# BSPD_Test_Board_rev3.net
KiCad netlist of a schematic drawn in EAGLE
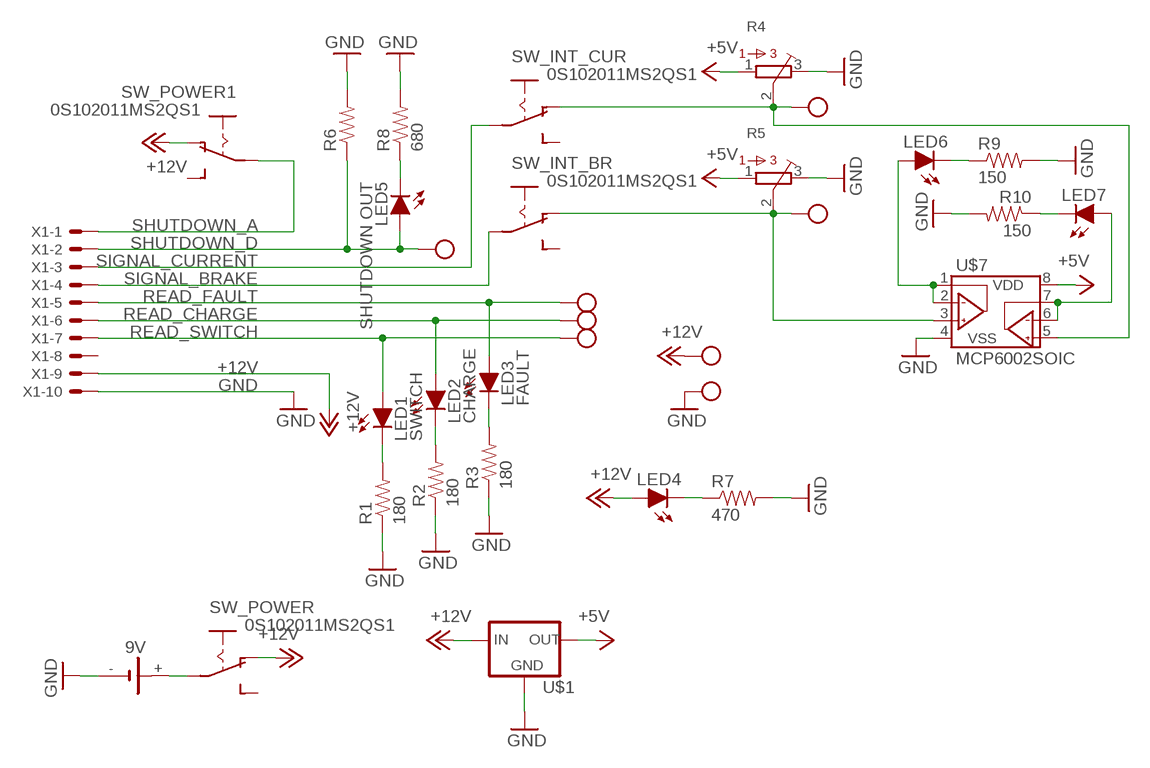
[diagram p0: schematic, sheet 1]

(export (version "E")
  (design (tool "Eeschema 10.0.6"))
  (components
    (comp (ref "9V")
      (value "1291-79")
      (footprint "eagle-import:1291-79")
      (libsource (lib "eagle-import") (part "1291-79"))
    )
    (comp (ref "LED1")
      (value "SWITCH")
      (footprint "eagle-import:LED-5MM")
      (libsource (lib "eagle-import") (part "LED-5MM"))
    )
    (comp (ref "LED2")
      (value "CHARGE")
      (footprint "eagle-import:LED-5MM")
      (libsource (lib "eagle-import") (part "LED-5MM"))
    )
    (comp (ref "LED3")
      (value "FAULT")
      (footprint "eagle-import:LED-5MM")
      (libsource (lib "eagle-import") (part "LED-5MM"))
    )
    (comp (ref "LED4")
      (value "LED-0805")
      (footprint "eagle-import:LED-805")
      (libsource (lib "eagle-import") (part "LED-0805"))
    )
    (comp (ref "LED5")
      (value "SHUTDOWN OUT")
      (footprint "eagle-import:LED-5MM")
      (libsource (lib "eagle-import") (part "LED-5MM"))
    )
    (comp (ref "LED6")
      (value "LED-0805")
      (footprint "eagle-import:LED-805")
      (libsource (lib "eagle-import") (part "LED-0805"))
    )
    (comp (ref "LED7")
      (value "LED-0805")
      (footprint "eagle-import:LED-805")
      (libsource (lib "eagle-import") (part "LED-0805"))
    )
    (comp (ref "R1")
      (value "180")
      (footprint "eagle-import:0805")
      (libsource (lib "eagle-import") (part "RESISTOR0805-RES"))
    )
    (comp (ref "R2")
      (value "180")
      (footprint "eagle-import:0805")
      (libsource (lib "eagle-import") (part "RESISTOR0805-RES"))
    )
    (comp (ref "R3")
      (value "180")
      (footprint "eagle-import:0805")
      (libsource (lib "eagle-import") (part "RESISTOR0805-RES"))
    )
    (comp (ref "R4")
      (value "TRIMPOT_3296C")
      (footprint "eagle-import:TRIMPOT_3296")
      (libsource (lib "eagle-import") (part "TRIMPOT_3296C"))
    )
    (comp (ref "R5")
      (value "TRIMPOT_3296C")
      (footprint "eagle-import:TRIMPOT_3296")
      (libsource (lib "eagle-import") (part "TRIMPOT_3296C"))
    )
    (comp (ref "R6")
      (value "RESISTORPTH-1/2W")
      (footprint "eagle-import:AXIAL-0.5")
      (libsource (lib "eagle-import") (part "RESISTORPTH-1/2W"))
    )
    (comp (ref "R7")
      (value "470")
      (footprint "eagle-import:0805")
      (libsource (lib "eagle-import") (part "RESISTOR0805-RES"))
    )
    (comp (ref "R8")
      (value "680")
      (footprint "eagle-import:0805")
      (libsource (lib "eagle-import") (part "RESISTOR0805-RES"))
    )
    (comp (ref "R9")
      (value "150")
      (footprint "eagle-import:0805")
      (libsource (lib "eagle-import") (part "RESISTOR0805-RES"))
    )
    (comp (ref "R10")
      (value "150")
      (footprint "eagle-import:0805")
      (libsource (lib "eagle-import") (part "RESISTOR0805-RES"))
    )
    (comp (ref "SW_INT_BR")
      (value "0S102011MS2QS1")
      (footprint "eagle-import:0S102011MS2QS1")
      (libsource (lib "eagle-import") (part "0S102011MS2QS1"))
    )
    (comp (ref "SW_INT_CUR")
      (value "0S102011MS2QS1")
      (footprint "eagle-import:0S102011MS2QS1")
      (libsource (lib "eagle-import") (part "0S102011MS2QS1"))
    )
    (comp (ref "SW_POWER")
      (value "0S102011MS2QS1")
      (footprint "eagle-import:0S102011MS2QS1")
      (libsource (lib "eagle-import") (part "0S102011MS2QS1"))
    )
    (comp (ref "SW_POWER1")
      (value "0S102011MS2QS1")
      (footprint "eagle-import:0S102011MS2QS1")
      (libsource (lib "eagle-import") (part "0S102011MS2QS1"))
    )
    (comp (ref "U$1")
      (value "5VREG_LM340-NLM340MPX-5.0/NOPB")
      (footprint "eagle-import:SOT223")
      (libsource (lib "eagle-import") (part "5VREG_LM340-NLM340MPX-5.0/NOPB"))
    )
    (comp (ref "U$2")
      (value "TEST_POINT")
      (footprint "eagle-import:TEST_POINT")
      (libsource (lib "eagle-import") (part "TEST_POINT"))
    )
    (comp (ref "U$3")
      (value "TEST_POINT")
      (footprint "eagle-import:TEST_POINT")
      (libsource (lib "eagle-import") (part "TEST_POINT"))
    )
    (comp (ref "U$4")
      (value "TEST_POINT")
      (footprint "eagle-import:TEST_POINT")
      (libsource (lib "eagle-import") (part "TEST_POINT"))
    )
    (comp (ref "U$5")
      (value "TEST_POINT")
      (footprint "eagle-import:TEST_POINT")
      (libsource (lib "eagle-import") (part "TEST_POINT"))
    )
    (comp (ref "U$6")
      (value "TEST_POINT")
      (footprint "eagle-import:TEST_POINT")
      (libsource (lib "eagle-import") (part "TEST_POINT"))
    )
    (comp (ref "U$7")
      (value "MCP6002SOIC")
      (footprint "eagle-import:SOIC-08")
      (libsource (lib "eagle-import") (part "MCP6002SOIC"))
    )
    (comp (ref "U$8")
      (value "TEST_POINT")
      (footprint "eagle-import:TEST_POINT")
      (libsource (lib "eagle-import") (part "TEST_POINT"))
    )
    (comp (ref "U$9")
      (value "TEST_POINT")
      (footprint "eagle-import:TEST_POINT")
      (libsource (lib "eagle-import") (part "TEST_POINT"))
    )
    (comp (ref "U$10")
      (value "TEST_POINT")
      (footprint "eagle-import:TEST_POINT")
      (libsource (lib "eagle-import") (part "TEST_POINT"))
    )
    (comp (ref "X1")
      (value "CONNECTOR-10")
      (footprint "eagle-import:MINIFIT_5566-10")
      (libsource (lib "eagle-import") (part "CONNECTOR-10"))
    )
  )
  (nets
    (net (code "1") (name "+5V") (class "Default")
      (node (ref "R4") (pin "1") (pinfunction "1_1") (pintype "passive"))
      (node (ref "R5") (pin "1") (pinfunction "1_1") (pintype "passive"))
      (node (ref "U$1") (pin "3") (pinfunction "OUT_3") (pintype "output"))
      (node (ref "U$7") (pin "8") (pinfunction "VDD_8") (pintype "passive"))
    )
    (net (code "2") (name "+12V") (class "Default")
      (node (ref "LED4") (pin "A") (pinfunction "A_A") (pintype "passive"))
      (node (ref "SW_POWER") (pin "P$1") (pinfunction "O_P$1") (pintype "passive"))
      (node (ref "SW_POWER1") (pin "P$1") (pinfunction "O_P$1") (pintype "passive"))
      (node (ref "U$1") (pin "1") (pinfunction "IN_1") (pintype "input"))
      (node (ref "U$5") (pin "P$1") (pinfunction "P$1_P$1") (pintype "bidirectional"))
      (node (ref "X1") (pin "9") (pinfunction "S_9") (pintype "passive"))
    )
    (net (code "3") (name "/READ_CHARGE") (class "Default")
      (node (ref "LED2") (pin "A") (pinfunction "A_A") (pintype "passive"))
      (node (ref "U$9") (pin "P$1") (pinfunction "P$1_P$1") (pintype "bidirectional"))
      (node (ref "X1") (pin "6") (pinfunction "S_6") (pintype "passive"))
    )
    (net (code "4") (name "/READ_FAULT") (class "Default")
      (node (ref "LED3") (pin "A") (pinfunction "A_A") (pintype "passive"))
      (node (ref "U$8") (pin "P$1") (pinfunction "P$1_P$1") (pintype "bidirectional"))
      (node (ref "X1") (pin "5") (pinfunction "S_5") (pintype "passive"))
    )
    (net (code "5") (name "/READ_SWITCH") (class "Default")
      (node (ref "LED1") (pin "A") (pinfunction "A_A") (pintype "passive"))
      (node (ref "U$10") (pin "P$1") (pinfunction "P$1_P$1") (pintype "bidirectional"))
      (node (ref "X1") (pin "7") (pinfunction "S_7") (pintype "passive"))
    )
    (net (code "6") (name "/SHUTDOWN_D") (class "Default")
      (node (ref "LED5") (pin "A") (pinfunction "A_A") (pintype "passive"))
      (node (ref "R6") (pin "P$1") (pinfunction "1_P$1") (pintype "passive"))
      (node (ref "U$4") (pin "P$1") (pinfunction "P$1_P$1") (pintype "bidirectional"))
      (node (ref "X1") (pin "2") (pinfunction "S_2") (pintype "passive"))
    )
    (net (code "7") (name "/SIGNAL_BRAKE") (class "Default")
      (node (ref "SW_INT_BR") (pin "P$2") (pinfunction "P_P$2") (pintype "passive"))
      (node (ref "X1") (pin "4") (pinfunction "S_4") (pintype "passive"))
    )
    (net (code "8") (name "/SIGNAL_CURRENT") (class "Default")
      (node (ref "SW_INT_CUR") (pin "P$2") (pinfunction "P_P$2") (pintype "passive"))
      (node (ref "X1") (pin "3") (pinfunction "S_3") (pintype "passive"))
    )
    (net (code "9") (name "GND") (class "Default")
      (node (ref "9V") (pin "-") (pinfunction "-_-") (pintype "passive"))
      (node (ref "R1") (pin "1") (pinfunction "1_1") (pintype "passive"))
      (node (ref "R10") (pin "2") (pinfunction "2_2") (pintype "passive"))
      (node (ref "R2") (pin "1") (pinfunction "1_1") (pintype "passive"))
      (node (ref "R3") (pin "1") (pinfunction "1_1") (pintype "passive"))
      (node (ref "R4") (pin "3") (pinfunction "3_3") (pintype "passive"))
      (node (ref "R5") (pin "3") (pinfunction "3_3") (pintype "passive"))
      (node (ref "R6") (pin "P$2") (pinfunction "2_P$2") (pintype "passive"))
      (node (ref "R7") (pin "2") (pinfunction "2_2") (pintype "passive"))
      (node (ref "R8") (pin "2") (pinfunction "2_2") (pintype "passive"))
      (node (ref "R9") (pin "2") (pinfunction "2_2") (pintype "passive"))
      (node (ref "U$1") (pin "2") (pinfunction "GND_2") (pintype "input"))
      (node (ref "U$1") (pin "4") (pinfunction "GND_4") (pintype "input"))
      (node (ref "U$6") (pin "P$1") (pinfunction "P$1_P$1") (pintype "bidirectional"))
      (node (ref "U$7") (pin "4") (pinfunction "VSS_4") (pintype "passive"))
      (node (ref "X1") (pin "10") (pinfunction "S_10") (pintype "passive"))
    )
    (net (code "10") (name "Net-(LED1-C)") (class "Default")
      (node (ref "LED1") (pin "K") (pinfunction "C_K") (pintype "passive"))
      (node (ref "R1") (pin "2") (pinfunction "2_2") (pintype "passive"))
    )
    (net (code "11") (name "Net-(LED2-C)") (class "Default")
      (node (ref "LED2") (pin "K") (pinfunction "C_K") (pintype "passive"))
      (node (ref "R2") (pin "2") (pinfunction "2_2") (pintype "passive"))
    )
    (net (code "12") (name "Net-(LED3-C)") (class "Default")
      (node (ref "LED3") (pin "K") (pinfunction "C_K") (pintype "passive"))
      (node (ref "R3") (pin "2") (pinfunction "2_2") (pintype "passive"))
    )
    (net (code "13") (name "Net-(LED4-PadC)") (class "Default")
      (node (ref "LED4") (pin "C") (pinfunction "C_C") (pintype "passive"))
      (node (ref "R7") (pin "1") (pinfunction "1_1") (pintype "passive"))
    )
    (net (code "14") (name "Net-(LED5-C)") (class "Default")
      (node (ref "LED5") (pin "K") (pinfunction "C_K") (pintype "passive"))
      (node (ref "R8") (pin "1") (pinfunction "1_1") (pintype "passive"))
    )
    (net (code "15") (name "Net-(LED6-PadC)") (class "Default")
      (node (ref "LED6") (pin "C") (pinfunction "C_C") (pintype "passive"))
      (node (ref "R9") (pin "1") (pinfunction "1_1") (pintype "passive"))
    )
    (net (code "16") (name "Net-(LED7-PadC)") (class "Default")
      (node (ref "LED7") (pin "C") (pinfunction "C_C") (pintype "passive"))
      (node (ref "R10") (pin "1") (pinfunction "1_1") (pintype "passive"))
    )
    (net (code "17") (name "Net-(SW_INT_BR-O)") (class "Default")
      (node (ref "R5") (pin "2") (pinfunction "2_2") (pintype "passive"))
      (node (ref "SW_INT_BR") (pin "P$1") (pinfunction "O_P$1") (pintype "passive"))
      (node (ref "U$3") (pin "P$1") (pinfunction "P$1_P$1") (pintype "bidirectional"))
      (node (ref "U$7") (pin "3") (pinfunction "VINA+_3") (pintype "passive"))
    )
    (net (code "18") (name "Net-(SW_INT_CUR-O)") (class "Default")
      (node (ref "R4") (pin "2") (pinfunction "2_2") (pintype "passive"))
      (node (ref "SW_INT_CUR") (pin "P$1") (pinfunction "O_P$1") (pintype "passive"))
      (node (ref "U$2") (pin "P$1") (pinfunction "P$1_P$1") (pintype "bidirectional"))
      (node (ref "U$7") (pin "5") (pinfunction "VINB+_5") (pintype "passive"))
    )
    (net (code "19") (name "Net-(SW_POWER-P)") (class "Default")
      (node (ref "9V") (pin "+") (pinfunction "+_+") (pintype "passive"))
      (node (ref "SW_POWER") (pin "P$2") (pinfunction "P_P$2") (pintype "passive"))
    )
    (net (code "20") (name "Net-(SW_POWER1-P)") (class "Default")
      (node (ref "SW_POWER1") (pin "P$2") (pinfunction "P_P$2") (pintype "passive"))
      (node (ref "X1") (pin "1") (pinfunction "S_1") (pintype "passive"))
    )
    (net (code "21") (name "Net-(U$7-VINA-)") (class "Default")
      (node (ref "LED6") (pin "A") (pinfunction "A_A") (pintype "passive"))
      (node (ref "U$7") (pin "1") (pinfunction "VOUTA_1") (pintype "passive"))
      (node (ref "U$7") (pin "2") (pinfunction "VINA-_2") (pintype "passive"))
    )
    (net (code "22") (name "Net-(U$7-VINB-)") (class "Default")
      (node (ref "LED7") (pin "A") (pinfunction "A_A") (pintype "passive"))
      (node (ref "U$7") (pin "6") (pinfunction "VINB-_6") (pintype "passive"))
      (node (ref "U$7") (pin "7") (pinfunction "VOUTB_7") (pintype "passive"))
    )
    (net (code "23") (name "unconnected-(SW_INT_BR-S-PadP$3)") (class "Default")
      (node (ref "SW_INT_BR") (pin "P$3") (pinfunction "S_P$3") (pintype "passive"))
    )
    (net (code "24") (name "unconnected-(SW_INT_CUR-S-PadP$3)") (class "Default")
      (node (ref "SW_INT_CUR") (pin "P$3") (pinfunction "S_P$3") (pintype "passive"))
    )
    (net (code "25") (name "unconnected-(SW_POWER-S-PadP$3)") (class "Default")
      (node (ref "SW_POWER") (pin "P$3") (pinfunction "S_P$3") (pintype "passive"))
    )
    (net (code "26") (name "unconnected-(SW_POWER1-S-PadP$3)") (class "Default")
      (node (ref "SW_POWER1") (pin "P$3") (pinfunction "S_P$3") (pintype "passive"))
    )
    (net (code "27") (name "unconnected-(X1I-S-Pad8)") (class "Default")
      (node (ref "X1") (pin "8") (pinfunction "S_8") (pintype "passive"))
    )
  )
)
